# conf.net
KiCad netlist of a schematic drawn in Altium Designer
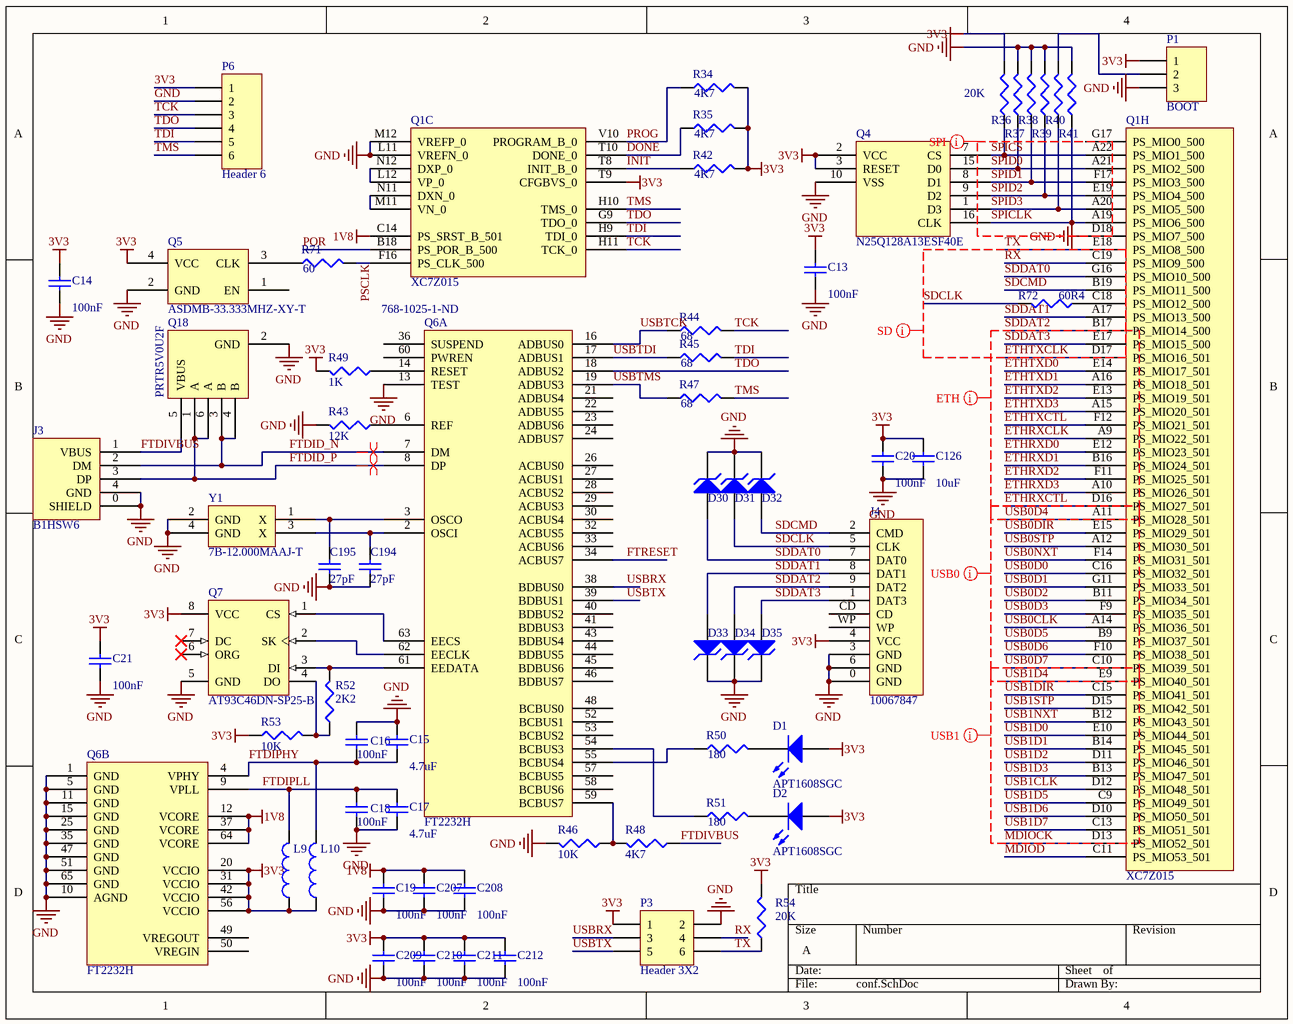
[diagram p0: conf.SchDoc]

(export (version "E")
  (design (tool "Eeschema 10.0.6"))
  (components
    (comp (ref "C13")
      (value "100nF")
      (footprint "CAPC1005X06L")
      (description "Capacitor")
      (fields (field (name "Comment") "Cap") (field (name "PUBLISHER") "Altium Limited"))
      (libsource (lib "Miscellaneous Devices") (part "Cap"))
    )
    (comp (ref "C14")
      (value "100nF")
      (footprint "CAPC1005X06L")
      (description "Capacitor")
      (fields (field (name "Comment") "Cap") (field (name "PUBLISHER") "Altium Limited"))
      (libsource (lib "Miscellaneous Devices") (part "Cap"))
    )
    (comp (ref "C15")
      (value "4.7uF")
      (footprint "CAPC1608X90N")
      (description "Capacitor")
      (fields (field (name "Comment") "GRM188R60J475ME19D") (field (name "PUBLISHER") "Altium Limited"))
      (libsource (lib "Miscellaneous Devices") (part "Cap"))
    )
    (comp (ref "C16")
      (value "100nF")
      (footprint "CAPC1005X06L")
      (description "Capacitor")
      (fields (field (name "Comment") "Cap") (field (name "PUBLISHER") "Altium Limited"))
      (libsource (lib "Miscellaneous Devices") (part "Cap"))
    )
    (comp (ref "C17")
      (value "4.7uF")
      (footprint "CAPC1608X90N")
      (description "Capacitor")
      (fields (field (name "Comment") "GRM188R60J475ME19D") (field (name "PUBLISHER") "Altium Limited"))
      (libsource (lib "Miscellaneous Devices") (part "Cap"))
    )
    (comp (ref "C18")
      (value "100nF")
      (footprint "CAPC1005X06L")
      (description "Capacitor")
      (fields (field (name "Comment") "Cap") (field (name "PUBLISHER") "Altium Limited"))
      (libsource (lib "Miscellaneous Devices") (part "Cap"))
    )
    (comp (ref "C19")
      (value "100nF")
      (footprint "CAPC1005X06L")
      (description "Capacitor")
      (fields (field (name "Comment") "Cap") (field (name "PUBLISHER") "Altium Limited"))
      (libsource (lib "Miscellaneous Devices") (part "Cap"))
    )
    (comp (ref "C20")
      (value "100nF")
      (footprint "CAPC1005X06L")
      (description "Capacitor")
      (fields (field (name "Comment") "Cap") (field (name "PUBLISHER") "Altium Limited"))
      (libsource (lib "Miscellaneous Devices") (part "Cap"))
    )
    (comp (ref "C21")
      (value "100nF")
      (footprint "CAPC1005X06L")
      (description "Capacitor")
      (fields (field (name "Comment") "Cap") (field (name "PUBLISHER") "Altium Limited"))
      (libsource (lib "Miscellaneous Devices") (part "Cap"))
    )
    (comp (ref "C126")
      (value "10uF")
      (footprint "CAPC1608X90N")
      (description "Capacitor")
      (fields (field (name "Comment") "GRM188R60G106ME47") (field (name "PUBLISHER") "Altium Limited"))
      (libsource (lib "Miscellaneous Devices") (part "Cap"))
    )
    (comp (ref "C194")
      (value "27pF")
      (footprint "CAPC1608X90N")
      (description "Capacitor")
      (fields (field (name "Comment") "CL10C270JB8NNNC") (field (name "PUBLISHER") "Altium Limited"))
      (libsource (lib "Miscellaneous Devices") (part "Cap"))
    )
    (comp (ref "C195")
      (value "27pF")
      (footprint "CAPC1608X90N")
      (description "Capacitor")
      (fields (field (name "Comment") "CL10C270JB8NNNC") (field (name "PUBLISHER") "Altium Limited"))
      (libsource (lib "Miscellaneous Devices") (part "Cap"))
    )
    (comp (ref "C207")
      (value "100nF")
      (footprint "CAPC1005X06L")
      (description "Capacitor")
      (fields (field (name "Comment") "Cap") (field (name "PUBLISHER") "Altium Limited"))
      (libsource (lib "Miscellaneous Devices") (part "Cap"))
    )
    (comp (ref "C208")
      (value "100nF")
      (footprint "CAPC1005X06L")
      (description "Capacitor")
      (fields (field (name "Comment") "Cap") (field (name "PUBLISHER") "Altium Limited"))
      (libsource (lib "Miscellaneous Devices") (part "Cap"))
    )
    (comp (ref "C209")
      (value "100nF")
      (footprint "CAPC1005X06L")
      (description "Capacitor")
      (fields (field (name "Comment") "Cap") (field (name "PUBLISHER") "Altium Limited"))
      (libsource (lib "Miscellaneous Devices") (part "Cap"))
    )
    (comp (ref "C210")
      (value "100nF")
      (footprint "CAPC1005X06L")
      (description "Capacitor")
      (fields (field (name "Comment") "Cap") (field (name "PUBLISHER") "Altium Limited"))
      (libsource (lib "Miscellaneous Devices") (part "Cap"))
    )
    (comp (ref "C211")
      (value "100nF")
      (footprint "CAPC1005X06L")
      (description "Capacitor")
      (fields (field (name "Comment") "Cap") (field (name "PUBLISHER") "Altium Limited"))
      (libsource (lib "Miscellaneous Devices") (part "Cap"))
    )
    (comp (ref "C212")
      (value "100nF")
      (footprint "CAPC1005X06L")
      (description "Capacitor")
      (fields (field (name "Comment") "Cap") (field (name "PUBLISHER") "Altium Limited"))
      (libsource (lib "Miscellaneous Devices") (part "Cap"))
    )
    (comp (ref "D1")
      (value "APT1608SGC")
      (footprint "LED-0603")
      (description "Typical RED, GREEN, YELLOW, AMBER GaAs LED")
      (fields (field (name "PUBLISHER") "Altium Limited"))
      (libsource (lib "Miscellaneous Devices") (part "LED2"))
    )
    (comp (ref "D2")
      (value "APT1608SGC")
      (footprint "LED-0603")
      (description "Typical RED, GREEN, YELLOW, AMBER GaAs LED")
      (fields (field (name "PUBLISHER") "Altium Limited"))
      (libsource (lib "Miscellaneous Devices") (part "LED2"))
    )
    (comp (ref "D30")
      (value "EZAEG2A")
      (footprint "CAPC1005X55N")
      (description "Zener Diode")
      (fields (field (name "PUBLISHER") "Altium Limited"))
      (libsource (lib "Miscellaneous Devices") (part "D Zener"))
    )
    (comp (ref "D31")
      (value "EZAEG2A")
      (footprint "CAPC1005X55N")
      (description "Zener Diode")
      (fields (field (name "PUBLISHER") "Altium Limited"))
      (libsource (lib "Miscellaneous Devices") (part "D Zener"))
    )
    (comp (ref "D32")
      (value "EZAEG2A")
      (footprint "CAPC1005X55N")
      (description "Zener Diode")
      (fields (field (name "PUBLISHER") "Altium Limited"))
      (libsource (lib "Miscellaneous Devices") (part "D Zener"))
    )
    (comp (ref "D33")
      (value "EZAEG2A")
      (footprint "CAPC1005X55N")
      (description "Zener Diode")
      (fields (field (name "PUBLISHER") "Altium Limited"))
      (libsource (lib "Miscellaneous Devices") (part "D Zener"))
    )
    (comp (ref "D34")
      (value "EZAEG2A")
      (footprint "CAPC1005X55N")
      (description "Zener Diode")
      (fields (field (name "PUBLISHER") "Altium Limited"))
      (libsource (lib "Miscellaneous Devices") (part "D Zener"))
    )
    (comp (ref "D35")
      (value "EZAEG2A")
      (footprint "CAPC1005X55N")
      (description "Zener Diode")
      (fields (field (name "PUBLISHER") "Altium Limited"))
      (libsource (lib "Miscellaneous Devices") (part "D Zener"))
    )
    (comp (ref "J3") (value "B1HSW6") (footprint "USB-B1HSW6") (libsource (lib "schlib") (part "USB")))
    (comp (ref "J4") (value "10067847") (footprint "SD-10067847") (libsource (lib "schlib") (part "SDCARD")))
    (comp (ref "L9")
      (value "BLM18SG121TN1")
      (footprint "CAPC1608X90N")
      (description "Inductor")
      (fields (field (name "PUBLISHER") "Altium Limited"))
      (libsource (lib "Miscellaneous Devices") (part "Inductor"))
    )
    (comp (ref "L10")
      (value "BLM18SG121TN1")
      (footprint "CAPC1608X90N")
      (description "Inductor")
      (fields (field (name "PUBLISHER") "Altium Limited"))
      (libsource (lib "Miscellaneous Devices") (part "Inductor"))
    )
    (comp (ref "P1")
      (value "BOOT")
      (footprint "HDR1X3")
      (description "Header, 3-Pin")
      (fields (field (name "PUBLISHER") "Altium Limited"))
      (libsource (lib "Miscellaneous Connectors") (part "Header 3"))
    )
    (comp (ref "P3")
      (value "Header 3X2")
      (footprint "HDR2X3")
      (description "Header, 3-Pin, Dual row")
      (fields (field (name "PUBLISHER") "Altium Limited"))
      (libsource (lib "Miscellaneous Connectors") (part "Header 3X2"))
    )
    (comp (ref "P6")
      (value "Header 6")
      (footprint "HDR1X6")
      (description "Header, 6-Pin")
      (fields (field (name "PUBLISHER") "Altium Limited"))
      (libsource (lib "Miscellaneous Connectors") (part "Header 6"))
    )
    (comp (ref "Q1") (value "XC7Z015") (footprint "BGA484x22") (libsource (lib "schlib") (part "XC7Z015")))
    (comp (ref "Q4")
      (value "N25Q128A13ESF40E")
      (footprint "SOP127P1030X265-16N")
      (libsource (lib "schlib") (part "QUADSPI"))
    )
    (comp (ref "Q5")
      (value "ASDMB-33.333MHZ-XY-T")
      (footprint "ASDMB")
      (libsource (lib "schlib") (part "osc"))
    )
    (comp (ref "Q6")
      (value "FT2232H")
      (footprint "FT2232H")
      (fields (field (name "SUPPLIER PART NUMBER 1") "768-1025-1-ND"))
      (libsource (lib "schlib") (part "FT2232H"))
    )
    (comp (ref "Q7")
      (value "AT93C46DN-SP25-B")
      (footprint "8S1_N")
      (description "1Kbit (128 x 8 or 64 x 16), 3-wire Bus Serial Automotive EEPROM, 2.5V, 8-Pin SOIC, Bulk")
      (fields (field (name "PUBLISHER") "Altium Limited"))
      (libsource (lib "Atmel Memory Serial EEPROM") (part "AT93C46DN-SP25-B"))
    )
    (comp (ref "Q18")
      (value "PRTR5V0U2F")
      (footprint "SOT886")
      (libsource (lib "schlib") (part "PRTR5V0U2F"))
    )
    (comp (ref "R34")
      (value "4K7")
      (footprint "J1-0603")
      (description "Resistor")
      (fields (field (name "Comment") "RC1608J472CS") (field (name "PUBLISHER") "Altium Limited"))
      (libsource (lib "Miscellaneous Devices") (part "Res3"))
    )
    (comp (ref "R35")
      (value "4K7")
      (footprint "J1-0603")
      (description "Resistor")
      (fields (field (name "Comment") "RC1608J472CS") (field (name "PUBLISHER") "Altium Limited"))
      (libsource (lib "Miscellaneous Devices") (part "Res3"))
    )
    (comp (ref "R36")
      (value "20K")
      (footprint "J1-0603")
      (description "Resistor")
      (fields (field (name "Comment") "RC1608F203CS") (field (name "PUBLISHER") "Altium Limited"))
      (libsource (lib "Miscellaneous Devices") (part "Res3"))
    )
    (comp (ref "R37")
      (value "RC1608F203CS")
      (footprint "J1-0603")
      (description "Resistor")
      (fields (field (name "PUBLISHER") "Altium Limited"))
      (libsource (lib "Miscellaneous Devices") (part "Res3"))
    )
    (comp (ref "R38")
      (value "RC1608F203CS")
      (footprint "J1-0603")
      (description "Resistor")
      (fields (field (name "PUBLISHER") "Altium Limited"))
      (libsource (lib "Miscellaneous Devices") (part "Res3"))
    )
    (comp (ref "R39")
      (value "RC1608F203CS")
      (footprint "J1-0603")
      (description "Resistor")
      (fields (field (name "PUBLISHER") "Altium Limited"))
      (libsource (lib "Miscellaneous Devices") (part "Res3"))
    )
    (comp (ref "R40")
      (value "RC1608F203CS")
      (footprint "J1-0603")
      (description "Resistor")
      (fields (field (name "PUBLISHER") "Altium Limited"))
      (libsource (lib "Miscellaneous Devices") (part "Res3"))
    )
    (comp (ref "R41")
      (value "RC1608F203CS")
      (footprint "J1-0603")
      (description "Resistor")
      (fields (field (name "PUBLISHER") "Altium Limited"))
      (libsource (lib "Miscellaneous Devices") (part "Res3"))
    )
    (comp (ref "R42")
      (value "4K7")
      (footprint "J1-0603")
      (description "Resistor")
      (fields (field (name "Comment") "RC1608J472CS") (field (name "PUBLISHER") "Altium Limited"))
      (libsource (lib "Miscellaneous Devices") (part "Res3"))
    )
    (comp (ref "R43")
      (value "12K")
      (footprint "J1-0603")
      (description "Resistor")
      (fields (field (name "Comment") "RC1608F123CS"))
      (libsource (lib "Miscellaneous Devices") (part "Res3"))
    )
    (comp (ref "R44")
      (value "68")
      (footprint "J1-0603")
      (description "Resistor")
      (fields (field (name "Comment") "RC1608J680CS") (field (name "PUBLISHER") "Altium Limited"))
      (libsource (lib "Miscellaneous Devices") (part "Res3"))
    )
    (comp (ref "R45")
      (value "68")
      (footprint "J1-0603")
      (description "Resistor")
      (fields (field (name "Comment") "RC1608J680CS") (field (name "PUBLISHER") "Altium Limited"))
      (libsource (lib "Miscellaneous Devices") (part "Res3"))
    )
    (comp (ref "R46")
      (value "10K")
      (footprint "J1-0603")
      (description "Resistor")
      (fields (field (name "Comment") "RC1608F103CS") (field (name "PUBLISHER") "Altium Limited"))
      (libsource (lib "Miscellaneous Devices") (part "Res3"))
    )
    (comp (ref "R47")
      (value "68")
      (footprint "J1-0603")
      (description "Resistor")
      (fields (field (name "Comment") "RC1608J680CS") (field (name "PUBLISHER") "Altium Limited"))
      (libsource (lib "Miscellaneous Devices") (part "Res3"))
    )
    (comp (ref "R48")
      (value "4K7")
      (footprint "J1-0603")
      (description "Resistor")
      (fields (field (name "Comment") "RC1608J472CS"))
      (libsource (lib "Miscellaneous Devices") (part "Res3"))
    )
    (comp (ref "R49")
      (value "1K")
      (footprint "J1-0603")
      (description "Resistor")
      (fields (field (name "Comment") "RC1608J102CS"))
      (libsource (lib "Miscellaneous Devices") (part "Res3"))
    )
    (comp (ref "R50")
      (value "180")
      (footprint "J1-0603")
      (description "Resistor")
      (fields (field (name "Comment") "RC1608J181CS") (field (name "PUBLISHER") "Altium Limited"))
      (libsource (lib "Miscellaneous Devices") (part "Res3"))
    )
    (comp (ref "R51")
      (value "180")
      (footprint "J1-0603")
      (description "Resistor")
      (fields (field (name "Comment") "RC1608J181CS") (field (name "PUBLISHER") "Altium Limited"))
      (libsource (lib "Miscellaneous Devices") (part "Res3"))
    )
    (comp (ref "R52")
      (value "2K2")
      (footprint "J1-0603")
      (description "Resistor")
      (fields (field (name "Comment") "RC1608J222CS") (field (name "PUBLISHER") "Altium Limited"))
      (libsource (lib "Miscellaneous Devices") (part "Res3"))
    )
    (comp (ref "R53")
      (value "10K")
      (footprint "J1-0603")
      (description "Resistor")
      (fields (field (name "Comment") "RC1608F103CS") (field (name "PUBLISHER") "Altium Limited"))
      (libsource (lib "Miscellaneous Devices") (part "Res3"))
    )
    (comp (ref "R54")
      (value "20K")
      (footprint "J1-0603")
      (description "Resistor")
      (fields (field (name "Comment") "RC1608F203CS") (field (name "PUBLISHER") "Altium Limited"))
      (libsource (lib "Miscellaneous Devices") (part "Res3"))
    )
    (comp (ref "R71")
      (value "60")
      (footprint "J1-0603")
      (description "Resistor")
      (fields (field (name "Comment") "RC1608F60R4CS"))
      (libsource (lib "Miscellaneous Devices") (part "Res3"))
    )
    (comp (ref "R72")
      (value "60R4")
      (footprint "CAPC1005X06L")
      (description "Resistor")
      (fields (field (name "Comment") "RC1005F60R4CS") (field (name "PUBLISHER") "Altium Limited"))
      (libsource (lib "Miscellaneous Devices") (part "Res3"))
    )
    (comp (ref "Y1") (value "7B-12.000MAAJ-T") (footprint "XTAL") (libsource (lib "schlib") (part "XTAL")))
  )
  (nets
    (net (code "1") (name "/DONE") (class "Default")
      (node (ref "Q1") (pin "T10") (pinfunction "DONE_0_T10") (pintype "passive"))
      (node (ref "R35") (pin "1") (pinfunction "1_1") (pintype "passive"))
    )
    (net (code "2") (name "/ETHRXCLK") (class "Default")
      (node (ref "Q1") (pin "A9") (pinfunction "PS_MIO22_501_A9") (pintype "passive"))
    )
    (net (code "3") (name "/ETHRXCTL") (class "Default")
      (node (ref "Q1") (pin "D16") (pinfunction "PS_MIO27_501_D16") (pintype "passive"))
    )
    (net (code "4") (name "/ETHRXD0") (class "Default")
      (node (ref "Q1") (pin "E12") (pinfunction "PS_MIO23_501_E12") (pintype "passive"))
    )
    (net (code "5") (name "/ETHRXD1") (class "Default")
      (node (ref "Q1") (pin "B16") (pinfunction "PS_MIO24_501_B16") (pintype "passive"))
    )
    (net (code "6") (name "/ETHRXD2") (class "Default")
      (node (ref "Q1") (pin "F11") (pinfunction "PS_MIO25_501_F11") (pintype "passive"))
    )
    (net (code "7") (name "/ETHRXD3") (class "Default")
      (node (ref "Q1") (pin "A10") (pinfunction "PS_MIO26_501_A10") (pintype "passive"))
    )
    (net (code "8") (name "/ETHTXCLK") (class "Default")
      (node (ref "Q1") (pin "D17") (pinfunction "PS_MIO16_501_D17") (pintype "passive"))
    )
    (net (code "9") (name "/ETHTXCTL") (class "Default")
      (node (ref "Q1") (pin "F12") (pinfunction "PS_MIO21_501_F12") (pintype "passive"))
    )
    (net (code "10") (name "/ETHTXD0") (class "Default")
      (node (ref "Q1") (pin "E14") (pinfunction "PS_MIO17_501_E14") (pintype "passive"))
    )
    (net (code "11") (name "/ETHTXD1") (class "Default")
      (node (ref "Q1") (pin "A16") (pinfunction "PS_MIO18_501_A16") (pintype "passive"))
    )
    (net (code "12") (name "/ETHTXD2") (class "Default")
      (node (ref "Q1") (pin "E13") (pinfunction "PS_MIO19_501_E13") (pintype "passive"))
    )
    (net (code "13") (name "/ETHTXD3") (class "Default")
      (node (ref "Q1") (pin "A15") (pinfunction "PS_MIO20_501_A15") (pintype "passive"))
    )
    (net (code "14") (name "/FTDID_N") (class "Default")
      (node (ref "J3") (pin "2") (pinfunction "DM_2") (pintype "passive"))
      (node (ref "Q18") (pin "3") (pinfunction "B_3") (pintype "passive"))
      (node (ref "Q18") (pin "4") (pinfunction "B_4") (pintype "passive"))
      (node (ref "Q6") (pin "7") (pinfunction "DM_7") (pintype "passive"))
    )
    (net (code "15") (name "/FTDID_P") (class "Default")
      (node (ref "J3") (pin "3") (pinfunction "DP_3") (pintype "passive"))
      (node (ref "Q18") (pin "1") (pinfunction "A_1") (pintype "passive"))
      (node (ref "Q18") (pin "6") (pinfunction "A_6") (pintype "passive"))
      (node (ref "Q6") (pin "8") (pinfunction "DP_8") (pintype "passive"))
    )
    (net (code "16") (name "/FTDIPHY") (class "Default")
      (node (ref "C15") (pin "1") (pinfunction "1_1") (pintype "passive"))
      (node (ref "C16") (pin "1") (pinfunction "1_1") (pintype "passive"))
      (node (ref "L10") (pin "2") (pinfunction "2_2") (pintype "passive"))
      (node (ref "Q6") (pin "4") (pinfunction "VPHY_4") (pintype "passive"))
    )
    (net (code "17") (name "/FTDIPLL") (class "Default")
      (node (ref "C17") (pin "2") (pinfunction "2_2") (pintype "passive"))
      (node (ref "C18") (pin "2") (pinfunction "2_2") (pintype "passive"))
      (node (ref "L9") (pin "2") (pinfunction "2_2") (pintype "passive"))
      (node (ref "Q6") (pin "9") (pinfunction "VPLL_9") (pintype "passive"))
    )
    (net (code "18") (name "/FTDIVBUS") (class "Default")
      (node (ref "J3") (pin "1") (pinfunction "VBUS_1") (pintype "passive"))
      (node (ref "Q18") (pin "5") (pinfunction "VBUS_5") (pintype "passive"))
      (node (ref "R48") (pin "1") (pinfunction "1_1") (pintype "passive"))
    )
    (net (code "19") (name "/FTRESET") (class "Default")
      (node (ref "Q6") (pin "34") (pinfunction "ACBUS7_34") (pintype "passive"))
    )
    (net (code "20") (name "/INIT") (class "Default")
      (node (ref "Q1") (pin "T8") (pinfunction "INIT_B_0_T8") (pintype "passive"))
      (node (ref "R42") (pin "1") (pinfunction "1_1") (pintype "passive"))
    )
    (net (code "21") (name "/MDIOCK") (class "Default")
      (node (ref "Q1") (pin "D13") (pinfunction "PS_MIO52_501_D13") (pintype "passive"))
    )
    (net (code "22") (name "/MDIOD") (class "Default")
      (node (ref "Q1") (pin "C11") (pinfunction "PS_MIO53_501_C11") (pintype "passive"))
    )
    (net (code "23") (name "/POR") (class "Default")
      (node (ref "Q1") (pin "B18") (pinfunction "PS_POR_B_500_B18") (pintype "passive"))
    )
    (net (code "24") (name "/PROG") (class "Default")
      (node (ref "Q1") (pin "V10") (pinfunction "PROGRAM_B_0_V10") (pintype "passive"))
      (node (ref "R34") (pin "1") (pinfunction "1_1") (pintype "passive"))
    )
    (net (code "25") (name "/PSCLK") (class "Default")
      (node (ref "Q1") (pin "F16") (pinfunction "PS_CLK_500_F16") (pintype "passive"))
      (node (ref "R71") (pin "2") (pinfunction "2_2") (pintype "passive"))
    )
    (net (code "26") (name "/RX") (class "Default")
      (node (ref "P3") (pin "4") (pinfunction "4_4") (pintype "passive"))
      (node (ref "Q1") (pin "C19") (pinfunction "PS_MIO9_500_C19") (pintype "passive"))
    )
    (net (code "27") (name "/SDCLK") (class "Default")
      (node (ref "D31") (pin "1") (pinfunction "A_1") (pintype "passive"))
      (node (ref "J4") (pin "5") (pinfunction "CLK_5") (pintype "passive"))
      (node (ref "R72") (pin "2") (pinfunction "2_2") (pintype "passive"))
    )
    (net (code "28") (name "/SDCMD") (class "Default")
      (node (ref "D32") (pin "1") (pinfunction "A_1") (pintype "passive"))
      (node (ref "J4") (pin "2") (pinfunction "CMD_2") (pintype "passive"))
      (node (ref "Q1") (pin "B19") (pinfunction "PS_MIO11_500_B19") (pintype "passive"))
    )
    (net (code "29") (name "/SDDAT0") (class "Default")
      (node (ref "D30") (pin "1") (pinfunction "A_1") (pintype "passive"))
      (node (ref "J4") (pin "7") (pinfunction "DAT0_7") (pintype "passive"))
      (node (ref "Q1") (pin "G16") (pinfunction "PS_MIO10_500_G16") (pintype "passive"))
    )
    (net (code "30") (name "/SDDAT1") (class "Default")
      (node (ref "D33") (pin "1") (pinfunction "A_1") (pintype "passive"))
      (node (ref "J4") (pin "8") (pinfunction "DAT1_8") (pintype "passive"))
      (node (ref "Q1") (pin "A17") (pinfunction "PS_MIO13_500_A17") (pintype "passive"))
    )
    (net (code "31") (name "/SDDAT2") (class "Default")
      (node (ref "D34") (pin "1") (pinfunction "A_1") (pintype "passive"))
      (node (ref "J4") (pin "9") (pinfunction "DAT2_9") (pintype "passive"))
      (node (ref "Q1") (pin "B17") (pinfunction "PS_MIO14_500_B17") (pintype "passive"))
    )
    (net (code "32") (name "/SDDAT3") (class "Default")
      (node (ref "D35") (pin "1") (pinfunction "A_1") (pintype "passive"))
      (node (ref "J4") (pin "1") (pinfunction "DAT3_1") (pintype "passive"))
      (node (ref "Q1") (pin "E17") (pinfunction "PS_MIO15_500_E17") (pintype "passive"))
    )
    (net (code "33") (name "/SPICLK") (class "Default")
      (node (ref "Q1") (pin "A19") (pinfunction "PS_MIO6_500_A19") (pintype "passive"))
      (node (ref "Q4") (pin "16") (pinfunction "CLK_16") (pintype "passive"))
      (node (ref "R41") (pin "1") (pinfunction "1_1") (pintype "passive"))
    )
    (net (code "34") (name "/SPICS") (class "Default")
      (node (ref "Q1") (pin "A22") (pinfunction "PS_MIO1_500_A22") (pintype "passive"))
      (node (ref "Q4") (pin "7") (pinfunction "CS_7") (pintype "passive"))
      (node (ref "R36") (pin "1") (pinfunction "1_1") (pintype "passive"))
    )
    (net (code "35") (name "/SPID0") (class "Default")
      (node (ref "Q1") (pin "A21") (pinfunction "PS_MIO2_500_A21") (pintype "passive"))
      (node (ref "Q4") (pin "15") (pinfunction "D0_15") (pintype "passive"))
      (node (ref "R37") (pin "1") (pinfunction "1_1") (pintype "passive"))
    )
    (net (code "36") (name "/SPID1") (class "Default")
      (node (ref "Q1") (pin "F17") (pinfunction "PS_MIO3_500_F17") (pintype "passive"))
      (node (ref "Q4") (pin "8") (pinfunction "D1_8") (pintype "passive"))
      (node (ref "R38") (pin "1") (pinfunction "1_1") (pintype "passive"))
    )
    (net (code "37") (name "/SPID2") (class "Default")
      (node (ref "Q1") (pin "E19") (pinfunction "PS_MIO4_500_E19") (pintype "passive"))
      (node (ref "Q4") (pin "9") (pinfunction "D2_9") (pintype "passive"))
      (node (ref "R39") (pin "1") (pinfunction "1_1") (pintype "passive"))
    )
    (net (code "38") (name "/SPID3") (class "Default")
      (node (ref "Q1") (pin "A20") (pinfunction "PS_MIO5_500_A20") (pintype "passive"))
      (node (ref "Q4") (pin "1") (pinfunction "D3_1") (pintype "passive"))
      (node (ref "R40") (pin "1") (pinfunction "1_1") (pintype "passive"))
    )
    (net (code "39") (name "/TCK") (class "Default")
      (node (ref "P6") (pin "3") (pinfunction "3_3") (pintype "passive"))
      (node (ref "Q1") (pin "H11") (pinfunction "TCK_0_H11") (pintype "passive"))
      (node (ref "R44") (pin "2") (pinfunction "2_2") (pintype "passive"))
    )
    (net (code "40") (name "/TDI") (class "Default")
      (node (ref "P6") (pin "5") (pinfunction "5_5") (pintype "passive"))
      (node (ref "Q1") (pin "H9") (pinfunction "TDI_0_H9") (pintype "passive"))
      (node (ref "R45") (pin "2") (pinfunction "2_2") (pintype "passive"))
    )
    (net (code "41") (name "/TDO") (class "Default")
      (node (ref "P6") (pin "4") (pinfunction "4_4") (pintype "passive"))
      (node (ref "Q1") (pin "G9") (pinfunction "TDO_0_G9") (pintype "passive"))
      (node (ref "Q6") (pin "18") (pinfunction "ADBUS2_18") (pintype "passive"))
    )
    (net (code "42") (name "/TMS") (class "Default")
      (node (ref "P6") (pin "6") (pinfunction "6_6") (pintype "passive"))
      (node (ref "Q1") (pin "H10") (pinfunction "TMS_0_H10") (pintype "passive"))
      (node (ref "R47") (pin "2") (pinfunction "2_2") (pintype "passive"))
    )
    (net (code "43") (name "/TX") (class "Default")
      (node (ref "P3") (pin "6") (pinfunction "6_6") (pintype "passive"))
      (node (ref "Q1") (pin "E18") (pinfunction "PS_MIO8_500_E18") (pintype "passive"))
      (node (ref "R54") (pin "1") (pinfunction "1_1") (pintype "passive"))
    )
    (net (code "44") (name "/USB0CLK") (class "Default")
      (node (ref "Q1") (pin "A14") (pinfunction "PS_MIO36_501_A14") (pintype "passive"))
    )
    (net (code "45") (name "/USB0D0") (class "Default")
      (node (ref "Q1") (pin "C16") (pinfunction "PS_MIO32_501_C16") (pintype "passive"))
    )
    (net (code "46") (name "/USB0D1") (class "Default")
      (node (ref "Q1") (pin "G11") (pinfunction "PS_MIO33_501_G11") (pintype "passive"))
    )
    (net (code "47") (name "/USB0D2") (class "Default")
      (node (ref "Q1") (pin "B11") (pinfunction "PS_MIO34_501_B11") (pintype "passive"))
    )
    (net (code "48") (name "/USB0D3") (class "Default")
      (node (ref "Q1") (pin "F9") (pinfunction "PS_MIO35_501_F9") (pintype "passive"))
    )
    (net (code "49") (name "/USB0D4") (class "Default")
      (node (ref "Q1") (pin "A11") (pinfunction "PS_MIO28_501_A11") (pintype "passive"))
    )
    (net (code "50") (name "/USB0D5") (class "Default")
      (node (ref "Q1") (pin "B9") (pinfunction "PS_MIO37_501_B9") (pintype "passive"))
    )
    (net (code "51") (name "/USB0D6") (class "Default")
      (node (ref "Q1") (pin "F10") (pinfunction "PS_MIO38_501_F10") (pintype "passive"))
    )
    (net (code "52") (name "/USB0D7") (class "Default")
      (node (ref "Q1") (pin "C10") (pinfunction "PS_MIO39_501_C10") (pintype "passive"))
    )
    (net (code "53") (name "/USB0DIR") (class "Default")
      (node (ref "Q1") (pin "E15") (pinfunction "PS_MIO29_501_E15") (pintype "passive"))
    )
    (net (code "54") (name "/USB0NXT") (class "Default")
      (node (ref "Q1") (pin "F14") (pinfunction "PS_MIO31_501_F14") (pintype "passive"))
    )
    (net (code "55") (name "/USB0STP") (class "Default")
      (node (ref "Q1") (pin "A12") (pinfunction "PS_MIO30_501_A12") (pintype "passive"))
    )
    (net (code "56") (name "/USB1CLK") (class "Default")
      (node (ref "Q1") (pin "D12") (pinfunction "PS_MIO48_501_D12") (pintype "passive"))
    )
    (net (code "57") (name "/USB1D0") (class "Default")
      (node (ref "Q1") (pin "E10") (pinfunction "PS_MIO44_501_E10") (pintype "passive"))
    )
    (net (code "58") (name "/USB1D1") (class "Default")
      (node (ref "Q1") (pin "B14") (pinfunction "PS_MIO45_501_B14") (pintype "passive"))
    )
    (net (code "59") (name "/USB1D2") (class "Default")
      (node (ref "Q1") (pin "D11") (pinfunction "PS_MIO46_501_D11") (pintype "passive"))
    )
    (net (code "60") (name "/USB1D3") (class "Default")
      (node (ref "Q1") (pin "B13") (pinfunction "PS_MIO47_501_B13") (pintype "passive"))
    )
    (net (code "61") (name "/USB1D4") (class "Default")
      (node (ref "Q1") (pin "E9") (pinfunction "PS_MIO40_501_E9") (pintype "passive"))
    )
    (net (code "62") (name "/USB1D5") (class "Default")
      (node (ref "Q1") (pin "C9") (pinfunction "PS_MIO49_501_C9") (pintype "passive"))
    )
    (net (code "63") (name "/USB1D6") (class "Default")
      (node (ref "Q1") (pin "D10") (pinfunction "PS_MIO50_501_D10") (pintype "passive"))
    )
    (net (code "64") (name "/USB1D7") (class "Default")
      (node (ref "Q1") (pin "C13") (pinfunction "PS_MIO51_501_C13") (pintype "passive"))
    )
    (net (code "65") (name "/USB1DIR") (class "Default")
      (node (ref "Q1") (pin "C15") (pinfunction "PS_MIO41_501_C15") (pintype "passive"))
    )
    (net (code "66") (name "/USB1NXT") (class "Default")
      (node (ref "Q1") (pin "B12") (pinfunction "PS_MIO43_501_B12") (pintype "passive"))
    )
    (net (code "67") (name "/USB1STP") (class "Default")
      (node (ref "Q1") (pin "D15") (pinfunction "PS_MIO42_501_D15") (pintype "passive"))
    )
    (net (code "68") (name "/USBRX") (class "Default")
      (node (ref "P3") (pin "3") (pinfunction "3_3") (pintype "passive"))
      (node (ref "Q6") (pin "38") (pinfunction "BDBUS0_38") (pintype "passive"))
    )
    (net (code "69") (name "/USBTCK") (class "Default")
      (node (ref "Q6") (pin "16") (pinfunction "ADBUS0_16") (pintype "passive"))
      (node (ref "R44") (pin "1") (pinfunction "1_1") (pintype "passive"))
    )
    (net (code "70") (name "/USBTDI") (class "Default")
      (node (ref "Q6") (pin "17") (pinfunction "ADBUS1_17") (pintype "passive"))
      (node (ref "R45") (pin "1") (pinfunction "1_1") (pintype "passive"))
    )
    (net (code "71") (name "/USBTMS") (class "Default")
      (node (ref "Q6") (pin "19") (pinfunction "ADBUS3_19") (pintype "passive"))
      (node (ref "R47") (pin "1") (pinfunction "1_1") (pintype "passive"))
    )
    (net (code "72") (name "/USBTX") (class "Default")
      (node (ref "P3") (pin "5") (pinfunction "5_5") (pintype "passive"))
      (node (ref "Q6") (pin "39") (pinfunction "BDBUS1_39") (pintype "passive"))
    )
    (net (code "73") (name "1V8") (class "Default")
      (node (ref "C19") (pin "1") (pinfunction "1_1") (pintype "passive"))
      (node (ref "C207") (pin "1") (pinfunction "1_1") (pintype "passive"))
      (node (ref "C208") (pin "1") (pinfunction "1_1") (pintype "passive"))
      (node (ref "Q1") (pin "C14") (pinfunction "PS_SRST_B_501_C14") (pintype "passive"))
      (node (ref "Q6") (pin "12") (pinfunction "VCORE_12") (pintype "passive"))
      (node (ref "Q6") (pin "37") (pinfunction "VCORE_37") (pintype "passive"))
      (node (ref "Q6") (pin "64") (pinfunction "VCORE_64") (pintype "passive"))
    )
    (net (code "74") (name "3V3") (class "Default")
      (node (ref "C126") (pin "2") (pinfunction "2_2") (pintype "passive"))
      (node (ref "C13") (pin "2") (pinfunction "2_2") (pintype "passive"))
      (node (ref "C14") (pin "2") (pinfunction "2_2") (pintype "passive"))
      (node (ref "C20") (pin "2") (pinfunction "2_2") (pintype "passive"))
      (node (ref "C209") (pin "1") (pinfunction "1_1") (pintype "passive"))
      (node (ref "C21") (pin "1") (pinfunction "1_1") (pintype "passive"))
      (node (ref "C210") (pin "1") (pinfunction "1_1") (pintype "passive"))
      (node (ref "C211") (pin "1") (pinfunction "1_1") (pintype "passive"))
      (node (ref "C212") (pin "1") (pinfunction "1_1") (pintype "passive"))
      (node (ref "D1") (pin "A") (pinfunction "A_A") (pintype "passive"))
      (node (ref "D2") (pin "A") (pinfunction "A_A") (pintype "passive"))
      (node (ref "J4") (pin "4") (pinfunction "VCC_4") (pintype "passive"))
      (node (ref "L10") (pin "1") (pinfunction "1_1") (pintype "passive"))
      (node (ref "L9") (pin "1") (pinfunction "1_1") (pintype "passive"))
      (node (ref "P1") (pin "1") (pinfunction "1_1") (pintype "passive"))
      (node (ref "P3") (pin "1") (pinfunction "1_1") (pintype "passive"))
      (node (ref "P6") (pin "1") (pinfunction "1_1") (pintype "passive"))
      (node (ref "Q1") (pin "T9") (pinfunction "CFGBVS_0_T9") (pintype "passive"))
      (node (ref "Q4") (pin "2") (pinfunction "VCC_2") (pintype "passive"))
      (node (ref "Q4") (pin "3") (pinfunction "RESET_3") (pintype "passive"))
      (node (ref "Q5") (pin "4") (pinfunction "VCC_4") (pintype "passive"))
      (node (ref "Q6") (pin "20") (pinfunction "VCCIO_20") (pintype "passive"))
      (node (ref "Q6") (pin "31") (pinfunction "VCCIO_31") (pintype "passive"))
      (node (ref "Q6") (pin "42") (pinfunction "VCCIO_42") (pintype "passive"))
      (node (ref "Q6") (pin "56") (pinfunction "VCCIO_56") (pintype "passive"))
      (node (ref "Q7") (pin "8") (pinfunction "VCC_8") (pintype "power_in"))
      (node (ref "R34") (pin "2") (pinfunction "2_2") (pintype "passive"))
      (node (ref "R35") (pin "2") (pinfunction "2_2") (pintype "passive"))
      (node (ref "R36") (pin "2") (pinfunction "2_2") (pintype "passive"))
      (node (ref "R42") (pin "2") (pinfunction "2_2") (pintype "passive"))
      (node (ref "R49") (pin "2") (pinfunction "2_2") (pintype "passive"))
      (node (ref "R53") (pin "1") (pinfunction "1_1") (pintype "passive"))
      (node (ref "R54") (pin "2") (pinfunction "2_2") (pintype "passive"))
    )
    (net (code "75") (name "GND") (class "Default")
      (node (ref "C126") (pin "1") (pinfunction "1_1") (pintype "passive"))
      (node (ref "C13") (pin "1") (pinfunction "1_1") (pintype "passive"))
      (node (ref "C14") (pin "1") (pinfunction "1_1") (pintype "passive"))
      (node (ref "C15") (pin "2") (pinfunction "2_2") (pintype "passive"))
      (node (ref "C16") (pin "2") (pinfunction "2_2") (pintype "passive"))
      (node (ref "C17") (pin "1") (pinfunction "1_1") (pintype "passive"))
      (node (ref "C18") (pin "1") (pinfunction "1_1") (pintype "passive"))
      (node (ref "C19") (pin "2") (pinfunction "2_2") (pintype "passive"))
      (node (ref "C194") (pin "2") (pinfunction "2_2") (pintype "passive"))
      (node (ref "C195") (pin "1") (pinfunction "1_1") (pintype "passive"))
      (node (ref "C20") (pin "1") (pinfunction "1_1") (pintype "passive"))
      (node (ref "C207") (pin "2") (pinfunction "2_2") (pintype "passive"))
      (node (ref "C208") (pin "2") (pinfunction "2_2") (pintype "passive"))
      (node (ref "C209") (pin "2") (pinfunction "2_2") (pintype "passive"))
      (node (ref "C21") (pin "2") (pinfunction "2_2") (pintype "passive"))
      (node (ref "C210") (pin "2") (pinfunction "2_2") (pintype "passive"))
      (node (ref "C211") (pin "2") (pinfunction "2_2") (pintype "passive"))
      (node (ref "C212") (pin "2") (pinfunction "2_2") (pintype "passive"))
      (node (ref "D30") (pin "2") (pinfunction "K_2") (pintype "passive"))
      (node (ref "D31") (pin "2") (pinfunction "K_2") (pintype "passive"))
      (node (ref "D32") (pin "2") (pinfunction "K_2") (pintype "passive"))
      (node (ref "D33") (pin "2") (pinfunction "K_2") (pintype "passive"))
      (node (ref "D34") (pin "2") (pinfunction "K_2") (pintype "passive"))
      (node (ref "D35") (pin "2") (pinfunction "K_2") (pintype "passive"))
      (node (ref "J3") (pin "0") (pinfunction "SHIELD_0") (pintype "passive"))
      (node (ref "J3") (pin "4") (pinfunction "GND_4") (pintype "passive"))
      (node (ref "J4") (pin "0") (pinfunction "GND_0") (pintype "passive"))
      (node (ref "J4") (pin "3") (pinfunction "GND_3") (pintype "passive"))
      (node (ref "J4") (pin "6") (pinfunction "GND_6") (pintype "passive"))
      (node (ref "P1") (pin "3") (pinfunction "3_3") (pintype "passive"))
      (node (ref "P3") (pin "2") (pinfunction "2_2") (pintype "passive"))
      (node (ref "P6") (pin "2") (pinfunction "2_2") (pintype "passive"))
      (node (ref "Q1") (pin "D18") (pinfunction "PS_MIO7_500_D18") (pintype "passive"))
      (node (ref "Q1") (pin "L11") (pinfunction "VREFN_0_L11") (pintype "passive"))
      (node (ref "Q1") (pin "M12") (pinfunction "VREFP_0_M12") (pintype "passive"))
      (node (ref "Q18") (pin "2") (pinfunction "GND_2") (pintype "passive"))
      (node (ref "Q4") (pin "10") (pinfunction "VSS_10") (pintype "passive"))
      (node (ref "Q5") (pin "2") (pinfunction "GND_2") (pintype "passive"))
      (node (ref "Q6") (pin "1") (pinfunction "GND_1") (pintype "passive"))
      (node (ref "Q6") (pin "10") (pinfunction "AGND_10") (pintype "passive"))
      (node (ref "Q6") (pin "11") (pinfunction "GND_11") (pintype "passive"))
      (node (ref "Q6") (pin "13") (pinfunction "TEST_13") (pintype "passive"))
      (node (ref "Q6") (pin "15") (pinfunction "GND_15") (pintype "passive"))
      (node (ref "Q6") (pin "25") (pinfunction "GND_25") (pintype "passive"))
      (node (ref "Q6") (pin "35") (pinfunction "GND_35") (pintype "passive"))
      (node (ref "Q6") (pin "47") (pinfunction "GND_47") (pintype "passive"))
      (node (ref "Q6") (pin "5") (pinfunction "GND_5") (pintype "passive"))
      (node (ref "Q6") (pin "51") (pinfunction "GND_51") (pintype "passive"))
      (node (ref "Q6") (pin "65") (pinfunction "GND_65") (pintype "passive"))
      (node (ref "Q7") (pin "5") (pinfunction "GND_5") (pintype "power_in"))
      (node (ref "R37") (pin "2") (pinfunction "2_2") (pintype "passive"))
      (node (ref "R38") (pin "2") (pinfunction "2_2") (pintype "passive"))
      (node (ref "R39") (pin "2") (pinfunction "2_2") (pintype "passive"))
      (node (ref "R41") (pin "2") (pinfunction "2_2") (pintype "passive"))
      (node (ref "R43") (pin "2") (pinfunction "2_2") (pintype "passive"))
      (node (ref "R46") (pin "2") (pinfunction "2_2") (pintype "passive"))
      (node (ref "Y1") (pin "2") (pinfunction "GND_2") (pintype "passive"))
      (node (ref "Y1") (pin "4") (pinfunction "GND_4") (pintype "passive"))
    )
    (net (code "76") (name "Net-(D1-PadK)") (class "Default")
      (node (ref "D1") (pin "K") (pinfunction "K_K") (pintype "passive"))
      (node (ref "R50") (pin "2") (pinfunction "2_2") (pintype "passive"))
    )
    (net (code "77") (name "Net-(D2-PadK)") (class "Default")
      (node (ref "D2") (pin "K") (pinfunction "K_K") (pintype "passive"))
      (node (ref "R51") (pin "2") (pinfunction "2_2") (pintype "passive"))
    )
    (net (code "78") (name "Net-(P1-Pad2)") (class "Default")
      (node (ref "P1") (pin "2") (pinfunction "2_2") (pintype "passive"))
      (node (ref "R40") (pin "2") (pinfunction "2_2") (pintype "passive"))
    )
    (net (code "79") (name "Net-(Q1C-DXN_0)") (class "Default")
      (node (ref "Q1") (pin "M11") (pinfunction "VN_0_M11") (pintype "passive"))
      (node (ref "Q1") (pin "N11") (pinfunction "DXN_0_N11") (pintype "passive"))
    )
    (net (code "80") (name "Net-(Q1C-DXP_0)") (class "Default")
      (node (ref "Q1") (pin "L12") (pinfunction "VP_0_L12") (pintype "passive"))
      (node (ref "Q1") (pin "N12") (pinfunction "DXP_0_N12") (pintype "passive"))
    )
    (net (code "81") (name "Net-(Q1H-PS_MIO12_500)") (class "Default")
      (node (ref "Q1") (pin "C18") (pinfunction "PS_MIO12_500_C18") (pintype "passive"))
      (node (ref "R72") (pin "1") (pinfunction "1_1") (pintype "passive"))
    )
    (net (code "82") (name "Net-(Q5-CLK)") (class "Default")
      (node (ref "Q5") (pin "3") (pinfunction "CLK_3") (pintype "passive"))
      (node (ref "R71") (pin "1") (pinfunction "1_1") (pintype "passive"))
    )
    (net (code "83") (name "Net-(Q6A-BCBUS3)") (class "Default")
      (node (ref "Q6") (pin "54") (pinfunction "BCBUS3_54") (pintype "passive"))
      (node (ref "R51") (pin "1") (pinfunction "1_1") (pintype "passive"))
    )
    (net (code "84") (name "Net-(Q6A-BCBUS4)") (class "Default")
      (node (ref "Q6") (pin "55") (pinfunction "BCBUS4_55") (pintype "passive"))
      (node (ref "R50") (pin "1") (pinfunction "1_1") (pintype "passive"))
    )
    (net (code "85") (name "Net-(Q6A-BCBUS7)") (class "Default")
      (node (ref "Q6") (pin "59") (pinfunction "BCBUS7_59") (pintype "passive"))
      (node (ref "R46") (pin "1") (pinfunction "1_1") (pintype "passive"))
      (node (ref "R48") (pin "2") (pinfunction "2_2") (pintype "passive"))
    )
    (net (code "86") (name "Net-(Q6A-EECLK)") (class "Default")
      (node (ref "Q6") (pin "62") (pinfunction "EECLK_62") (pintype "passive"))
      (node (ref "Q7") (pin "2") (pinfunction "SK_2") (pintype "input"))
    )
    (net (code "87") (name "Net-(Q6A-EECS)") (class "Default")
      (node (ref "Q6") (pin "63") (pinfunction "EECS_63") (pintype "passive"))
      (node (ref "Q7") (pin "1") (pinfunction "CS_1") (pintype "input"))
    )
    (net (code "88") (name "Net-(Q6A-EEDATA)") (class "Default")
      (node (ref "Q6") (pin "61") (pinfunction "EEDATA_61") (pintype "passive"))
      (node (ref "Q7") (pin "3") (pinfunction "DI_3") (pintype "input"))
      (node (ref "R52") (pin "2") (pinfunction "2_2") (pintype "passive"))
    )
    (net (code "89") (name "Net-(Q6A-OSCI)") (class "Default")
      (node (ref "C194") (pin "1") (pinfunction "1_1") (pintype "passive"))
      (node (ref "Q6") (pin "2") (pinfunction "OSCI_2") (pintype "passive"))
      (node (ref "Y1") (pin "3") (pinfunction "X_3") (pintype "passive"))
    )
    (net (code "90") (name "Net-(Q6A-OSCO)") (class "Default")
      (node (ref "C195") (pin "2") (pinfunction "2_2") (pintype "passive"))
      (node (ref "Q6") (pin "3") (pinfunction "OSCO_3") (pintype "passive"))
      (node (ref "Y1") (pin "1") (pinfunction "X_1") (pintype "passive"))
    )
    (net (code "91") (name "Net-(Q6A-REF)") (class "Default")
      (node (ref "Q6") (pin "6") (pinfunction "REF_6") (pintype "passive"))
      (node (ref "R43") (pin "1") (pinfunction "1_1") (pintype "passive"))
    )
    (net (code "92") (name "Net-(Q6A-RESET)") (class "Default")
      (node (ref "Q6") (pin "14") (pinfunction "RESET_14") (pintype "passive"))
      (node (ref "R49") (pin "1") (pinfunction "1_1") (pintype "passive"))
    )
    (net (code "93") (name "Net-(Q7-DO)") (class "Default")
      (node (ref "Q7") (pin "4") (pinfunction "DO_4") (pintype "tri_state"))
      (node (ref "R52") (pin "1") (pinfunction "1_1") (pintype "passive"))
      (node (ref "R53") (pin "2") (pinfunction "2_2") (pintype "passive"))
    )
    (net (code "94") (name "unconnected-(J4-PadCD)") (class "Default")
      (node (ref "J4") (pin "CD") (pinfunction "CD_CD") (pintype "passive"))
    )
    (net (code "95") (name "unconnected-(J4-PadWP)") (class "Default")
      (node (ref "J4") (pin "WP") (pinfunction "WP_WP") (pintype "passive"))
    )
    (net (code "96") (name "unconnected-(Q1H-PS_MIO0_500-PadG17)") (class "Default")
      (node (ref "Q1") (pin "G17") (pinfunction "PS_MIO0_500_G17") (pintype "passive"))
    )
    (net (code "97") (name "unconnected-(Q5-EN-Pad1)") (class "Default")
      (node (ref "Q5") (pin "1") (pinfunction "EN_1") (pintype "passive"))
    )
    (net (code "98") (name "unconnected-(Q6A-ACBUS0-Pad26)") (class "Default")
      (node (ref "Q6") (pin "26") (pinfunction "ACBUS0_26") (pintype "passive"))
    )
    (net (code "99") (name "unconnected-(Q6A-ACBUS1-Pad27)") (class "Default")
      (node (ref "Q6") (pin "27") (pinfunction "ACBUS1_27") (pintype "passive"))
    )
    (net (code "100") (name "unconnected-(Q6A-ACBUS2-Pad28)") (class "Default")
      (node (ref "Q6") (pin "28") (pinfunction "ACBUS2_28") (pintype "passive"))
    )
    (net (code "101") (name "unconnected-(Q6A-ACBUS3-Pad29)") (class "Default")
      (node (ref "Q6") (pin "29") (pinfunction "ACBUS3_29") (pintype "passive"))
    )
    (net (code "102") (name "unconnected-(Q6A-ACBUS4-Pad30)") (class "Default")
      (node (ref "Q6") (pin "30") (pinfunction "ACBUS4_30") (pintype "passive"))
    )
    (net (code "103") (name "unconnected-(Q6A-ACBUS5-Pad32)") (class "Default")
      (node (ref "Q6") (pin "32") (pinfunction "ACBUS5_32") (pintype "passive"))
    )
    (net (code "104") (name "unconnected-(Q6A-ACBUS6-Pad33)") (class "Default")
      (node (ref "Q6") (pin "33") (pinfunction "ACBUS6_33") (pintype "passive"))
    )
    (net (code "105") (name "unconnected-(Q6A-ADBUS4-Pad21)") (class "Default")
      (node (ref "Q6") (pin "21") (pinfunction "ADBUS4_21") (pintype "passive"))
    )
    (net (code "106") (name "unconnected-(Q6A-ADBUS5-Pad22)") (class "Default")
      (node (ref "Q6") (pin "22") (pinfunction "ADBUS5_22") (pintype "passive"))
    )
    (net (code "107") (name "unconnected-(Q6A-ADBUS6-Pad23)") (class "Default")
      (node (ref "Q6") (pin "23") (pinfunction "ADBUS6_23") (pintype "passive"))
    )
    (net (code "108") (name "unconnected-(Q6A-ADBUS7-Pad24)") (class "Default")
      (node (ref "Q6") (pin "24") (pinfunction "ADBUS7_24") (pintype "passive"))
    )
    (net (code "109") (name "unconnected-(Q6A-BCBUS0-Pad48)") (class "Default")
      (node (ref "Q6") (pin "48") (pinfunction "BCBUS0_48") (pintype "passive"))
    )
    (net (code "110") (name "unconnected-(Q6A-BCBUS1-Pad52)") (class "Default")
      (node (ref "Q6") (pin "52") (pinfunction "BCBUS1_52") (pintype "passive"))
    )
    (net (code "111") (name "unconnected-(Q6A-BCBUS2-Pad53)") (class "Default")
      (node (ref "Q6") (pin "53") (pinfunction "BCBUS2_53") (pintype "passive"))
    )
    (net (code "112") (name "unconnected-(Q6A-BCBUS5-Pad57)") (class "Default")
      (node (ref "Q6") (pin "57") (pinfunction "BCBUS5_57") (pintype "passive"))
    )
    (net (code "113") (name "unconnected-(Q6A-BCBUS6-Pad58)") (class "Default")
      (node (ref "Q6") (pin "58") (pinfunction "BCBUS6_58") (pintype "passive"))
    )
    (net (code "114") (name "unconnected-(Q6A-BDBUS2-Pad40)") (class "Default")
      (node (ref "Q6") (pin "40") (pinfunction "BDBUS2_40") (pintype "passive"))
    )
    (net (code "115") (name "unconnected-(Q6A-BDBUS3-Pad41)") (class "Default")
      (node (ref "Q6") (pin "41") (pinfunction "BDBUS3_41") (pintype "passive"))
    )
    (net (code "116") (name "unconnected-(Q6A-BDBUS4-Pad43)") (class "Default")
      (node (ref "Q6") (pin "43") (pinfunction "BDBUS4_43") (pintype "passive"))
    )
    (net (code "117") (name "unconnected-(Q6A-BDBUS5-Pad44)") (class "Default")
      (node (ref "Q6") (pin "44") (pinfunction "BDBUS5_44") (pintype "passive"))
    )
    (net (code "118") (name "unconnected-(Q6A-BDBUS6-Pad45)") (class "Default")
      (node (ref "Q6") (pin "45") (pinfunction "BDBUS6_45") (pintype "passive"))
    )
    (net (code "119") (name "unconnected-(Q6A-BDBUS7-Pad46)") (class "Default")
      (node (ref "Q6") (pin "46") (pinfunction "BDBUS7_46") (pintype "passive"))
    )
    (net (code "120") (name "unconnected-(Q6A-PWREN-Pad60)") (class "Default")
      (node (ref "Q6") (pin "60") (pinfunction "PWREN_60") (pintype "passive"))
    )
    (net (code "121") (name "unconnected-(Q6A-SUSPEND-Pad36)") (class "Default")
      (node (ref "Q6") (pin "36") (pinfunction "SUSPEND_36") (pintype "passive"))
    )
    (net (code "122") (name "unconnected-(Q6B-VREGIN-Pad50)") (class "Default")
      (node (ref "Q6") (pin "50") (pinfunction "VREGIN_50") (pintype "passive"))
    )
    (net (code "123") (name "unconnected-(Q6B-VREGOUT-Pad49)") (class "Default")
      (node (ref "Q6") (pin "49") (pinfunction "VREGOUT_49") (pintype "passive"))
    )
    (net (code "124") (name "unconnected-(Q7-DC-Pad7)") (class "Default")
      (node (ref "Q7") (pin "7") (pinfunction "DC_7") (pintype "input+no_connect"))
    )
    (net (code "125") (name "unconnected-(Q7-ORG-Pad6)") (class "Default")
      (node (ref "Q7") (pin "6") (pinfunction "ORG_6") (pintype "input+no_connect"))
    )
  )
)
